# sync.net
KiCad netlist of a schematic drawn in Altium Designer
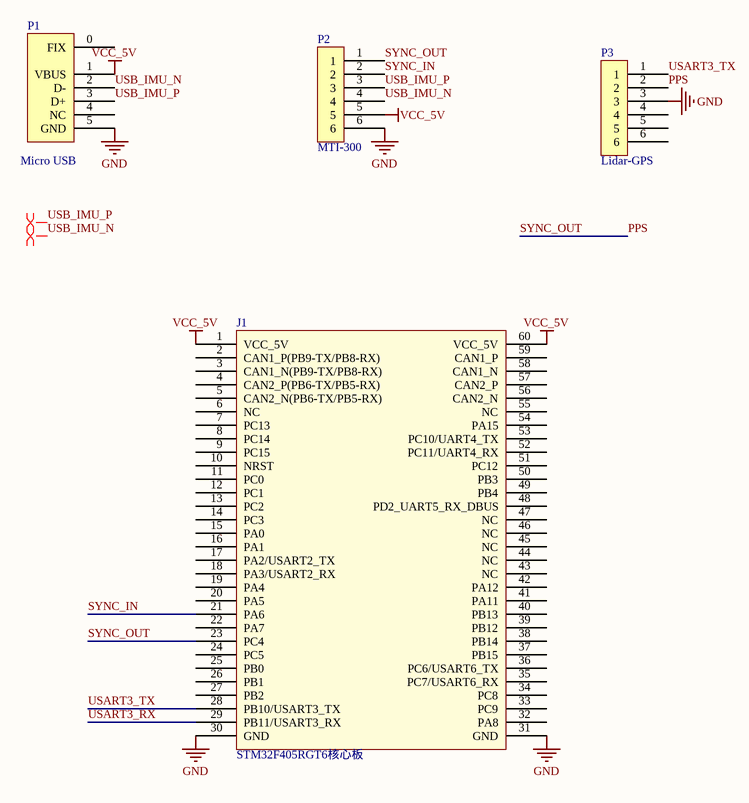
[diagram p0: sync.SchDoc]

(export (version "E")
  (design (tool "Eeschema 10.0.6"))
  (components
    (comp (ref "J1")
      (value "STM32F405RGT6核心板")
      (footprint "3710F060037G0FR01")
      (description "3710(F/M)060037G0FR01")
      (libsource (lib "Connectors") (part "STM32F405RGT6核心板"))
    )
    (comp (ref "P1")
      (value "Micro USB")
      (footprint "Micro USB")
      (description "Micro USB底座")
      (libsource (lib "Devices") (part "Micro USB"))
    )
    (comp (ref "P2")
      (value "MTI-300")
      (footprint "KF128-3.81-6P")
      (description "KF-6P")
      (libsource (lib "Connectors") (part "KF-6P"))
    )
    (comp (ref "P3")
      (value "Lidar-GPS")
      (footprint "FPC1.0-2H-WS-6P")
      (description "SH1.0-6P")
      (libsource (lib "Connectors") (part "SH1.0-6P"))
    )
  )
  (nets
    (net (code "1") (name "/PPS") (class "Default")
      (node (ref "J1") (pin "23") (pinfunction "PC4_23") (pintype "passive"))
      (node (ref "P2") (pin "1") (pinfunction "1_1") (pintype "passive"))
      (node (ref "P3") (pin "2") (pinfunction "2_2") (pintype "passive"))
    )
    (net (code "2") (name "/SYNC_IN") (class "Default")
      (node (ref "J1") (pin "21") (pinfunction "PA6_21") (pintype "passive"))
      (node (ref "P2") (pin "2") (pinfunction "2_2") (pintype "passive"))
    )
    (net (code "3") (name "/USART3_RX") (class "Default")
      (node (ref "J1") (pin "29") (pinfunction "PB11/USART3_RX_29") (pintype "passive"))
    )
    (net (code "4") (name "/USART3_TX") (class "Default")
      (node (ref "J1") (pin "28") (pinfunction "PB10/USART3_TX_28") (pintype "passive"))
      (node (ref "P3") (pin "1") (pinfunction "1_1") (pintype "passive"))
    )
    (net (code "5") (name "/USB_IMU_N") (class "Default")
      (node (ref "P1") (pin "2") (pinfunction "D-_2") (pintype "passive"))
      (node (ref "P2") (pin "4") (pinfunction "4_4") (pintype "passive"))
    )
    (net (code "6") (name "/USB_IMU_P") (class "Default")
      (node (ref "P1") (pin "3") (pinfunction "D+_3") (pintype "passive"))
      (node (ref "P2") (pin "3") (pinfunction "3_3") (pintype "passive"))
    )
    (net (code "7") (name "GND") (class "Default")
      (node (ref "J1") (pin "30") (pinfunction "GND_30") (pintype "passive"))
      (node (ref "J1") (pin "31") (pinfunction "GND_31") (pintype "passive"))
      (node (ref "P1") (pin "5") (pinfunction "GND_5") (pintype "passive"))
      (node (ref "P2") (pin "6") (pinfunction "6_6") (pintype "passive"))
      (node (ref "P3") (pin "3") (pinfunction "3_3") (pintype "passive"))
    )
    (net (code "8") (name "VCC_5V") (class "Default")
      (node (ref "J1") (pin "1") (pinfunction "VCC_5V_1") (pintype "passive"))
      (node (ref "J1") (pin "60") (pinfunction "VCC_5V_60") (pintype "passive"))
      (node (ref "P1") (pin "1") (pinfunction "VBUS_1") (pintype "passive"))
      (node (ref "P2") (pin "5") (pinfunction "5_5") (pintype "passive"))
    )
    (net (code "9") (name "unconnected-(J1-CAN1_N(PB9-TX{slash}PB8-RX)-Pad3)") (class "Default")
      (node (ref "J1") (pin "3") (pinfunction "CAN1_N(PB9-TX/PB8-RX)_3") (pintype "passive"))
    )
    (net (code "10") (name "unconnected-(J1-CAN1_N-Pad58)") (class "Default")
      (node (ref "J1") (pin "58") (pinfunction "CAN1_N_58") (pintype "passive"))
    )
    (net (code "11") (name "unconnected-(J1-CAN1_P(PB9-TX{slash}PB8-RX)-Pad2)") (class "Default")
      (node (ref "J1") (pin "2") (pinfunction "CAN1_P(PB9-TX/PB8-RX)_2") (pintype "passive"))
    )
    (net (code "12") (name "unconnected-(J1-CAN1_P-Pad59)") (class "Default")
      (node (ref "J1") (pin "59") (pinfunction "CAN1_P_59") (pintype "passive"))
    )
    (net (code "13") (name "unconnected-(J1-CAN2_N(PB6-TX{slash}PB5-RX)-Pad5)") (class "Default")
      (node (ref "J1") (pin "5") (pinfunction "CAN2_N(PB6-TX/PB5-RX)_5") (pintype "passive"))
    )
    (net (code "14") (name "unconnected-(J1-CAN2_N-Pad56)") (class "Default")
      (node (ref "J1") (pin "56") (pinfunction "CAN2_N_56") (pintype "passive"))
    )
    (net (code "15") (name "unconnected-(J1-CAN2_P(PB6-TX{slash}PB5-RX)-Pad4)") (class "Default")
      (node (ref "J1") (pin "4") (pinfunction "CAN2_P(PB6-TX/PB5-RX)_4") (pintype "passive"))
    )
    (net (code "16") (name "unconnected-(J1-CAN2_P-Pad57)") (class "Default")
      (node (ref "J1") (pin "57") (pinfunction "CAN2_P_57") (pintype "passive"))
    )
    (net (code "17") (name "unconnected-(J1-NC-Pad6)") (class "Default")
      (node (ref "J1") (pin "6") (pinfunction "NC_6") (pintype "passive"))
    )
    (net (code "18") (name "unconnected-(J1-NC-Pad43)") (class "Default")
      (node (ref "J1") (pin "43") (pinfunction "NC_43") (pintype "passive"))
    )
    (net (code "19") (name "unconnected-(J1-NC-Pad44)") (class "Default")
      (node (ref "J1") (pin "44") (pinfunction "NC_44") (pintype "passive"))
    )
    (net (code "20") (name "unconnected-(J1-NC-Pad45)") (class "Default")
      (node (ref "J1") (pin "45") (pinfunction "NC_45") (pintype "passive"))
    )
    (net (code "21") (name "unconnected-(J1-NC-Pad46)") (class "Default")
      (node (ref "J1") (pin "46") (pinfunction "NC_46") (pintype "passive"))
    )
    (net (code "22") (name "unconnected-(J1-NC-Pad47)") (class "Default")
      (node (ref "J1") (pin "47") (pinfunction "NC_47") (pintype "passive"))
    )
    (net (code "23") (name "unconnected-(J1-NC-Pad55)") (class "Default")
      (node (ref "J1") (pin "55") (pinfunction "NC_55") (pintype "passive"))
    )
    (net (code "24") (name "unconnected-(J1-NRST-Pad10)") (class "Default")
      (node (ref "J1") (pin "10") (pinfunction "NRST_10") (pintype "passive"))
    )
    (net (code "25") (name "unconnected-(J1-PA0-Pad15)") (class "Default")
      (node (ref "J1") (pin "15") (pinfunction "PA0_15") (pintype "passive"))
    )
    (net (code "26") (name "unconnected-(J1-PA1-Pad16)") (class "Default")
      (node (ref "J1") (pin "16") (pinfunction "PA1_16") (pintype "passive"))
    )
    (net (code "27") (name "unconnected-(J1-PA2{slash}USART2_TX-Pad17)") (class "Default")
      (node (ref "J1") (pin "17") (pinfunction "PA2/USART2_TX_17") (pintype "passive"))
    )
    (net (code "28") (name "unconnected-(J1-PA3{slash}USART2_RX-Pad18)") (class "Default")
      (node (ref "J1") (pin "18") (pinfunction "PA3/USART2_RX_18") (pintype "passive"))
    )
    (net (code "29") (name "unconnected-(J1-PA4-Pad19)") (class "Default")
      (node (ref "J1") (pin "19") (pinfunction "PA4_19") (pintype "passive"))
    )
    (net (code "30") (name "unconnected-(J1-PA5-Pad20)") (class "Default")
      (node (ref "J1") (pin "20") (pinfunction "PA5_20") (pintype "passive"))
    )
    (net (code "31") (name "unconnected-(J1-PA7-Pad22)") (class "Default")
      (node (ref "J1") (pin "22") (pinfunction "PA7_22") (pintype "passive"))
    )
    (net (code "32") (name "unconnected-(J1-PA8-Pad32)") (class "Default")
      (node (ref "J1") (pin "32") (pinfunction "PA8_32") (pintype "passive"))
    )
    (net (code "33") (name "unconnected-(J1-PA11-Pad41)") (class "Default")
      (node (ref "J1") (pin "41") (pinfunction "PA11_41") (pintype "passive"))
    )
    (net (code "34") (name "unconnected-(J1-PA12-Pad42)") (class "Default")
      (node (ref "J1") (pin "42") (pinfunction "PA12_42") (pintype "passive"))
    )
    (net (code "35") (name "unconnected-(J1-PA15-Pad54)") (class "Default")
      (node (ref "J1") (pin "54") (pinfunction "PA15_54") (pintype "passive"))
    )
    (net (code "36") (name "unconnected-(J1-PB0-Pad25)") (class "Default")
      (node (ref "J1") (pin "25") (pinfunction "PB0_25") (pintype "passive"))
    )
    (net (code "37") (name "unconnected-(J1-PB1-Pad26)") (class "Default")
      (node (ref "J1") (pin "26") (pinfunction "PB1_26") (pintype "passive"))
    )
    (net (code "38") (name "unconnected-(J1-PB2-Pad27)") (class "Default")
      (node (ref "J1") (pin "27") (pinfunction "PB2_27") (pintype "passive"))
    )
    (net (code "39") (name "unconnected-(J1-PB3-Pad50)") (class "Default")
      (node (ref "J1") (pin "50") (pinfunction "PB3_50") (pintype "passive"))
    )
    (net (code "40") (name "unconnected-(J1-PB4-Pad49)") (class "Default")
      (node (ref "J1") (pin "49") (pinfunction "PB4_49") (pintype "passive"))
    )
    (net (code "41") (name "unconnected-(J1-PB12-Pad39)") (class "Default")
      (node (ref "J1") (pin "39") (pinfunction "PB12_39") (pintype "passive"))
    )
    (net (code "42") (name "unconnected-(J1-PB13-Pad40)") (class "Default")
      (node (ref "J1") (pin "40") (pinfunction "PB13_40") (pintype "passive"))
    )
    (net (code "43") (name "unconnected-(J1-PB14-Pad38)") (class "Default")
      (node (ref "J1") (pin "38") (pinfunction "PB14_38") (pintype "passive"))
    )
    (net (code "44") (name "unconnected-(J1-PB15-Pad37)") (class "Default")
      (node (ref "J1") (pin "37") (pinfunction "PB15_37") (pintype "passive"))
    )
    (net (code "45") (name "unconnected-(J1-PC0-Pad11)") (class "Default")
      (node (ref "J1") (pin "11") (pinfunction "PC0_11") (pintype "passive"))
    )
    (net (code "46") (name "unconnected-(J1-PC1-Pad12)") (class "Default")
      (node (ref "J1") (pin "12") (pinfunction "PC1_12") (pintype "passive"))
    )
    (net (code "47") (name "unconnected-(J1-PC2-Pad13)") (class "Default")
      (node (ref "J1") (pin "13") (pinfunction "PC2_13") (pintype "passive"))
    )
    (net (code "48") (name "unconnected-(J1-PC3-Pad14)") (class "Default")
      (node (ref "J1") (pin "14") (pinfunction "PC3_14") (pintype "passive"))
    )
    (net (code "49") (name "unconnected-(J1-PC5-Pad24)") (class "Default")
      (node (ref "J1") (pin "24") (pinfunction "PC5_24") (pintype "passive"))
    )
    (net (code "50") (name "unconnected-(J1-PC6{slash}USART6_TX-Pad36)") (class "Default")
      (node (ref "J1") (pin "36") (pinfunction "PC6/USART6_TX_36") (pintype "passive"))
    )
    (net (code "51") (name "unconnected-(J1-PC7{slash}USART6_RX-Pad35)") (class "Default")
      (node (ref "J1") (pin "35") (pinfunction "PC7/USART6_RX_35") (pintype "passive"))
    )
    (net (code "52") (name "unconnected-(J1-PC8-Pad34)") (class "Default")
      (node (ref "J1") (pin "34") (pinfunction "PC8_34") (pintype "passive"))
    )
    (net (code "53") (name "unconnected-(J1-PC9-Pad33)") (class "Default")
      (node (ref "J1") (pin "33") (pinfunction "PC9_33") (pintype "passive"))
    )
    (net (code "54") (name "unconnected-(J1-PC10{slash}UART4_TX-Pad53)") (class "Default")
      (node (ref "J1") (pin "53") (pinfunction "PC10/UART4_TX_53") (pintype "passive"))
    )
    (net (code "55") (name "unconnected-(J1-PC11{slash}UART4_RX-Pad52)") (class "Default")
      (node (ref "J1") (pin "52") (pinfunction "PC11/UART4_RX_52") (pintype "passive"))
    )
    (net (code "56") (name "unconnected-(J1-PC12-Pad51)") (class "Default")
      (node (ref "J1") (pin "51") (pinfunction "PC12_51") (pintype "passive"))
    )
    (net (code "57") (name "unconnected-(J1-PC13-Pad7)") (class "Default")
      (node (ref "J1") (pin "7") (pinfunction "PC13_7") (pintype "passive"))
    )
    (net (code "58") (name "unconnected-(J1-PC14-Pad8)") (class "Default")
      (node (ref "J1") (pin "8") (pinfunction "PC14_8") (pintype "passive"))
    )
    (net (code "59") (name "unconnected-(J1-PC15-Pad9)") (class "Default")
      (node (ref "J1") (pin "9") (pinfunction "PC15_9") (pintype "passive"))
    )
    (net (code "60") (name "unconnected-(J1-PD2_UART5_RX_DBUS-Pad48)") (class "Default")
      (node (ref "J1") (pin "48") (pinfunction "PD2_UART5_RX_DBUS_48") (pintype "passive"))
    )
    (net (code "61") (name "unconnected-(P1-FIX-Pad0)") (class "Default")
      (node (ref "P1") (pin "0") (pinfunction "FIX_0") (pintype "passive"))
    )
    (net (code "62") (name "unconnected-(P1-NC-Pad4)") (class "Default")
      (node (ref "P1") (pin "4") (pinfunction "NC_4") (pintype "passive"))
    )
    (net (code "63") (name "unconnected-(P3-Pad4)") (class "Default")
      (node (ref "P3") (pin "4") (pinfunction "4_4") (pintype "passive"))
    )
    (net (code "64") (name "unconnected-(P3-Pad5)") (class "Default")
      (node (ref "P3") (pin "5") (pinfunction "5_5") (pintype "passive"))
    )
    (net (code "65") (name "unconnected-(P3-Pad6)") (class "Default")
      (node (ref "P3") (pin "6") (pinfunction "6_6") (pintype "passive"))
    )
  )
)
